# InverterControl_RevA.net
KiCad netlist of a schematic drawn in EAGLE
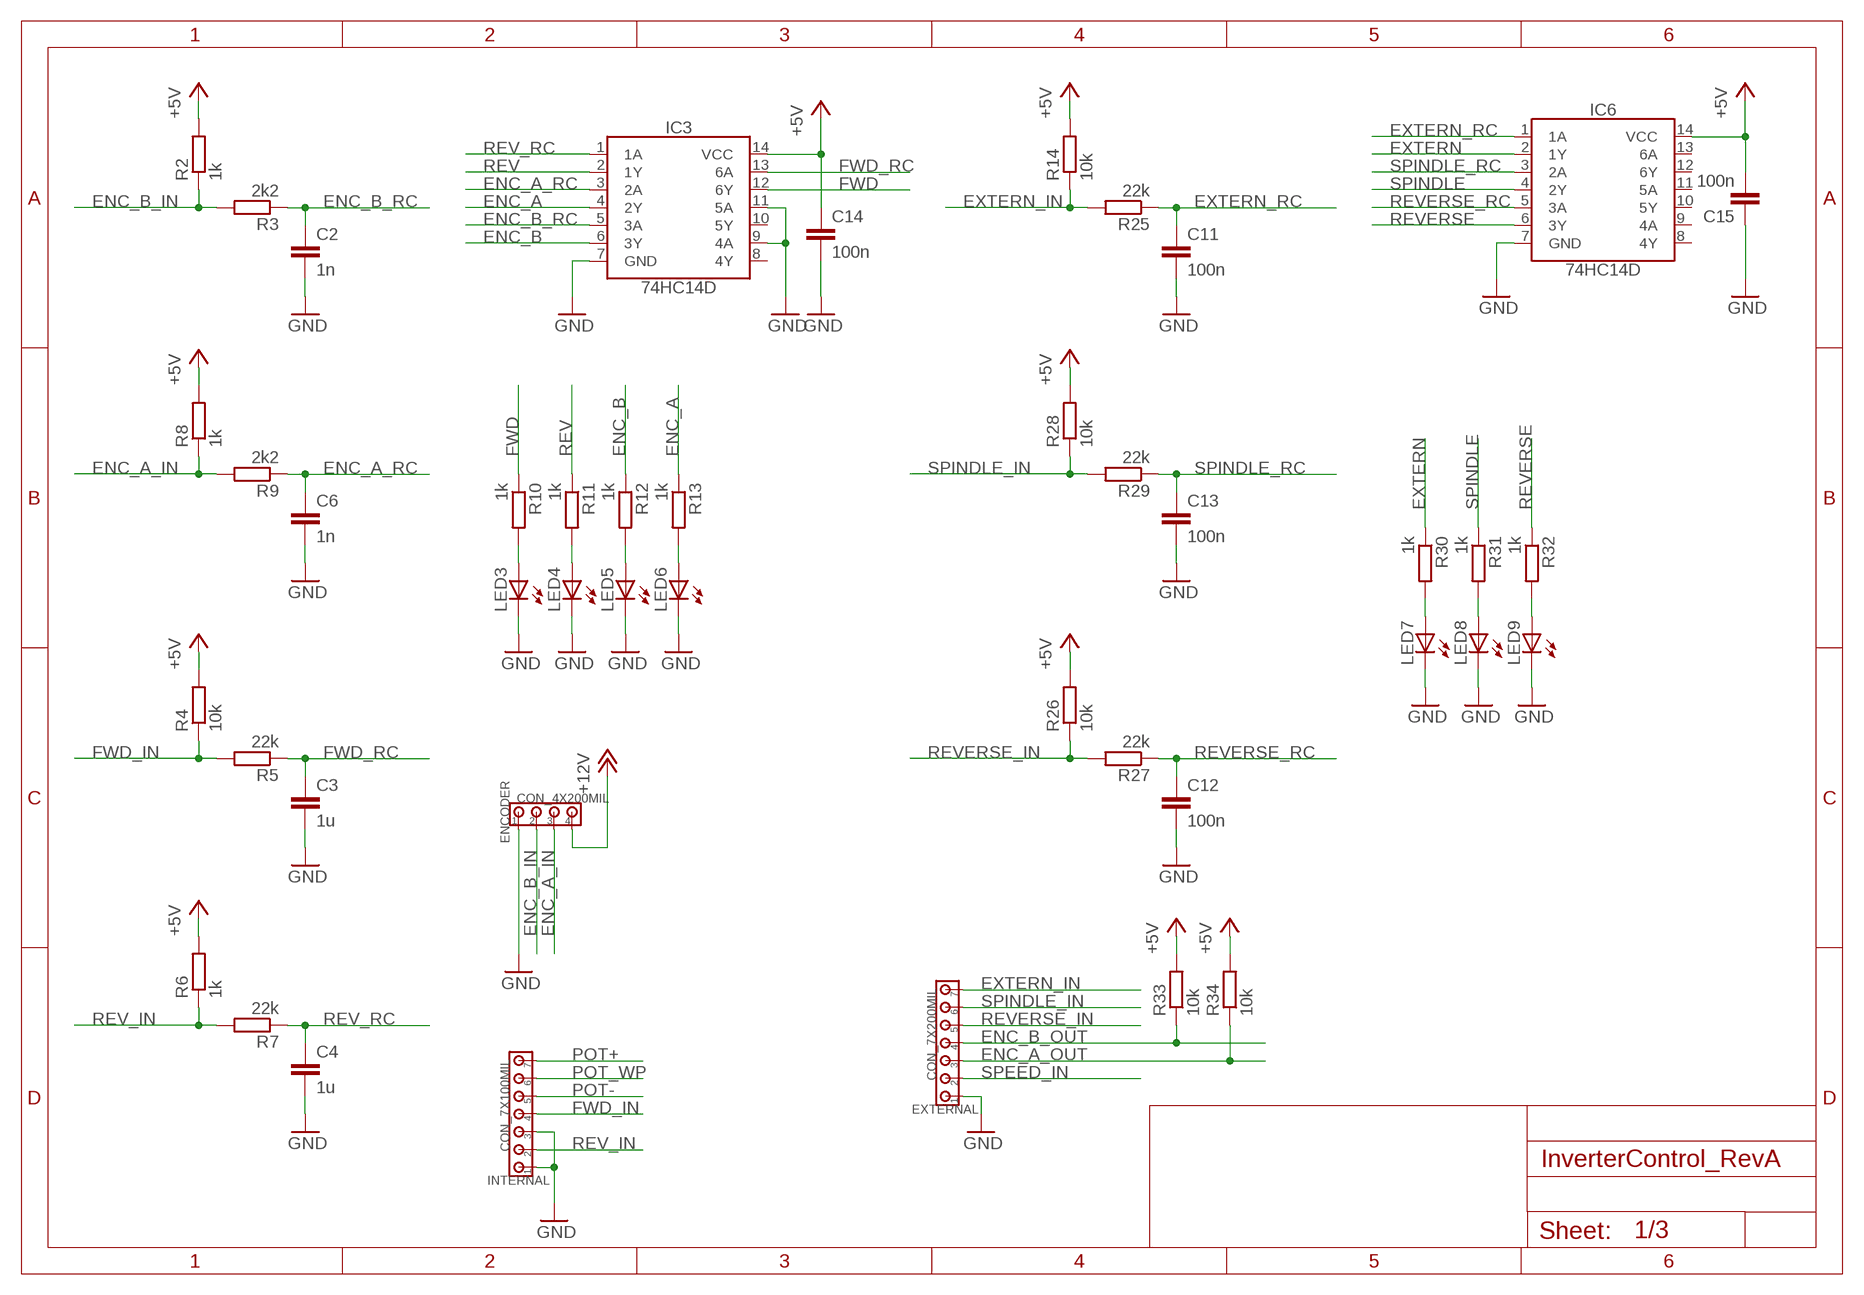
[diagram p0: schematic, sheet 1]
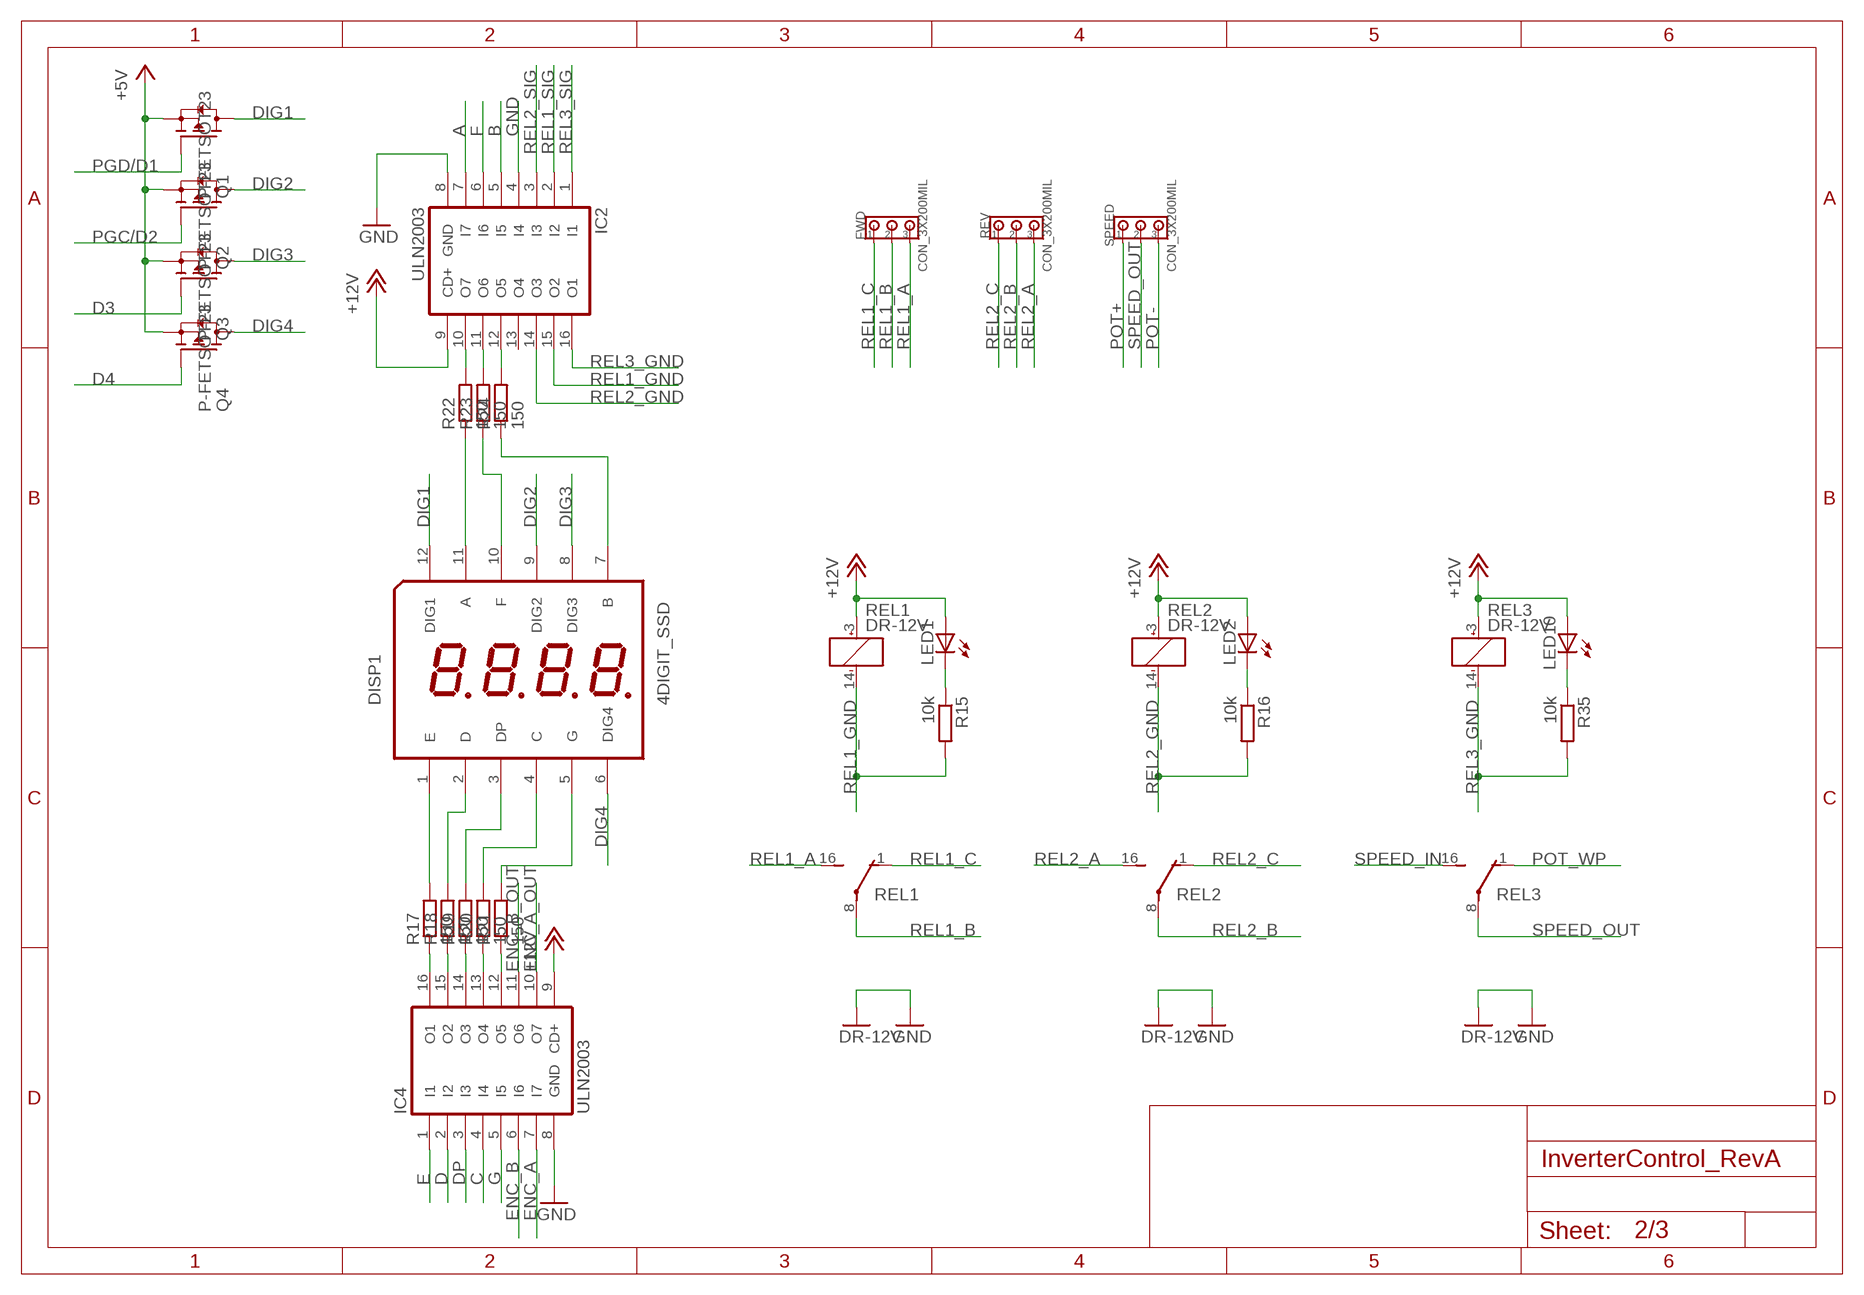
[diagram p1: schematic, sheet 2]
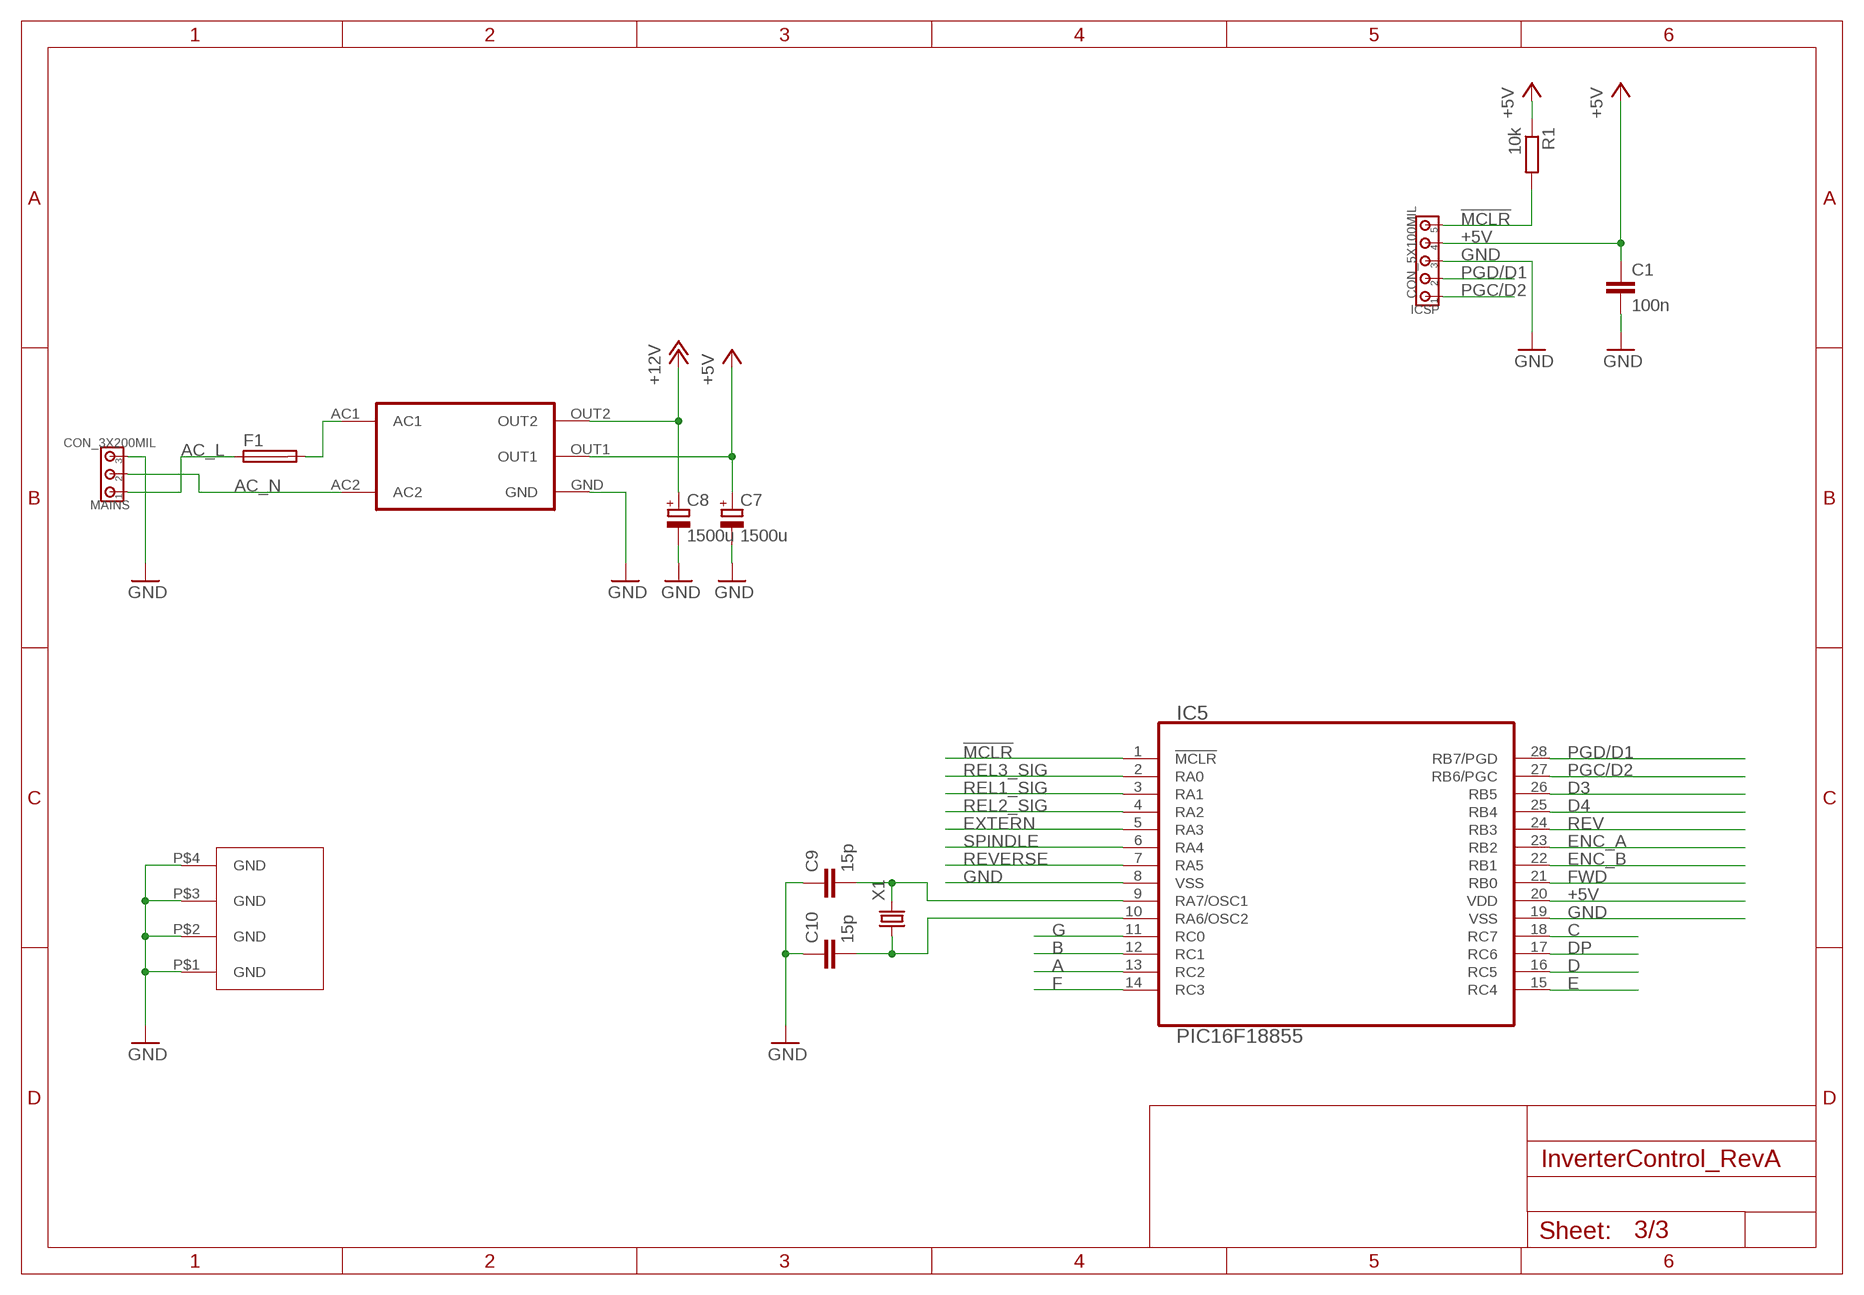
[diagram p2: schematic, sheet 3]

(export (version "E")
  (design (tool "Eeschema 10.0.6"))
  (components
    (comp (ref "ACDC1")
      (value "MYRRA47246")
      (footprint "eagle-import:MYRRA47000")
      (libsource (lib "eagle-import") (part "MYRRA47246"))
    )
    (comp (ref "C1")
      (value "100n")
      (footprint "eagle-import:C0805")
      (libsource (lib "eagle-import") (part "CC0805"))
    )
    (comp (ref "C7")
      (value "1500u")
      (footprint "eagle-import:10MM")
      (libsource (lib "eagle-import") (part "C_POLARIZED10MM"))
    )
    (comp (ref "C8")
      (value "1500u")
      (footprint "eagle-import:10MM")
      (libsource (lib "eagle-import") (part "C_POLARIZED10MM"))
    )
    (comp (ref "C9")
      (value "15p")
      (footprint "eagle-import:C0805")
      (libsource (lib "eagle-import") (part "CC0805"))
    )
    (comp (ref "C10")
      (value "15p")
      (footprint "eagle-import:C0805")
      (libsource (lib "eagle-import") (part "CC0805"))
    )
    (comp (ref "F1")
      (value "SH22,5")
      (footprint "eagle-import:SH22,5")
      (fields (field (name "MF") "SCHURTER") (field (name "MPN") "0031.8201"))
      (libsource (lib "eagle-import") (part "SH22,5"))
    )
    (comp (ref "IC5")
      (value "PIC16F18855")
      (footprint "eagle-import:SO28W")
      (libsource (lib "eagle-import") (part "PIC16F18855"))
    )
    (comp (ref "ICSP")
      (value "CON_5X100MIL")
      (footprint "eagle-import:100MIL_5X")
      (libsource (lib "eagle-import") (part "CON_5X100MIL"))
    )
    (comp (ref "MAINS")
      (value "CON_3X200MIL")
      (footprint "eagle-import:200MIL_3X")
      (libsource (lib "eagle-import") (part "CON_3X200MIL"))
    )
    (comp (ref "R1")
      (value "10k")
      (footprint "eagle-import:R0805")
      (libsource (lib "eagle-import") (part "RESISTORR0805"))
    )
    (comp (ref "U$1")
      (value "PCB_SPEED_METER")
      (footprint "eagle-import:PBC_SPEED_METER")
      (libsource (lib "eagle-import") (part "PCB_SPEED_METER"))
    )
    (comp (ref "X1")
      (value "CRYSTAL5X3.2MM")
      (footprint "eagle-import:5X3.2MM")
      (libsource (lib "eagle-import") (part "CRYSTAL5X3.2MM"))
    )
    (comp (ref "DISP1")
      (value "4DIGIT_SSD")
      (footprint "eagle-import:4DIGIT_SSD")
      (libsource (lib "eagle-import") (part "4DIGIT_SSD"))
    )
    (comp (ref "FWD")
      (value "CON_3X200MIL")
      (footprint "eagle-import:200MIL_3X")
      (libsource (lib "eagle-import") (part "CON_3X200MIL"))
    )
    (comp (ref "IC2")
      (value "ULN2003")
      (footprint "eagle-import:SO16")
      (libsource (lib "eagle-import") (part "ULN2003"))
    )
    (comp (ref "IC4")
      (value "ULN2003")
      (footprint "eagle-import:SO16")
      (libsource (lib "eagle-import") (part "ULN2003"))
    )
    (comp (ref "LED1")
      (value "LED0805")
      (footprint "eagle-import:LED0805")
      (libsource (lib "eagle-import") (part "LED0805"))
    )
    (comp (ref "LED2")
      (value "LED0805")
      (footprint "eagle-import:LED0805")
      (libsource (lib "eagle-import") (part "LED0805"))
    )
    (comp (ref "LED10")
      (value "LED0805")
      (footprint "eagle-import:LED0805")
      (libsource (lib "eagle-import") (part "LED0805"))
    )
    (comp (ref "Q1")
      (value "P-FETSOT23")
      (footprint "eagle-import:SOT23")
      (libsource (lib "eagle-import") (part "P-FETSOT23"))
    )
    (comp (ref "Q2")
      (value "P-FETSOT23")
      (footprint "eagle-import:SOT23")
      (libsource (lib "eagle-import") (part "P-FETSOT23"))
    )
    (comp (ref "Q3")
      (value "P-FETSOT23")
      (footprint "eagle-import:SOT23")
      (libsource (lib "eagle-import") (part "P-FETSOT23"))
    )
    (comp (ref "Q4")
      (value "P-FETSOT23")
      (footprint "eagle-import:SOT23")
      (libsource (lib "eagle-import") (part "P-FETSOT23"))
    )
    (comp (ref "R15")
      (value "10k")
      (footprint "eagle-import:R0805")
      (libsource (lib "eagle-import") (part "RESISTORR0805"))
    )
    (comp (ref "R16")
      (value "10k")
      (footprint "eagle-import:R0805")
      (libsource (lib "eagle-import") (part "RESISTORR0805"))
    )
    (comp (ref "R17")
      (value "150")
      (footprint "eagle-import:R0805")
      (libsource (lib "eagle-import") (part "RESISTORR0805"))
    )
    (comp (ref "R18")
      (value "150")
      (footprint "eagle-import:R0805")
      (libsource (lib "eagle-import") (part "RESISTORR0805"))
    )
    (comp (ref "R19")
      (value "150")
      (footprint "eagle-import:R0805")
      (libsource (lib "eagle-import") (part "RESISTORR0805"))
    )
    (comp (ref "R20")
      (value "150")
      (footprint "eagle-import:R0805")
      (libsource (lib "eagle-import") (part "RESISTORR0805"))
    )
    (comp (ref "R21")
      (value "150")
      (footprint "eagle-import:R0805")
      (libsource (lib "eagle-import") (part "RESISTORR0805"))
    )
    (comp (ref "R22")
      (value "150")
      (footprint "eagle-import:R0805")
      (libsource (lib "eagle-import") (part "RESISTORR0805"))
    )
    (comp (ref "R23")
      (value "150")
      (footprint "eagle-import:R0805")
      (libsource (lib "eagle-import") (part "RESISTORR0805"))
    )
    (comp (ref "R24")
      (value "150")
      (footprint "eagle-import:R0805")
      (libsource (lib "eagle-import") (part "RESISTORR0805"))
    )
    (comp (ref "R35")
      (value "10k")
      (footprint "eagle-import:R0805")
      (libsource (lib "eagle-import") (part "RESISTORR0805"))
    )
    (comp (ref "REL1")
      (value "DR-12V")
      (footprint "eagle-import:DR-12V")
      (libsource (lib "eagle-import") (part "DR-12V"))
    )
    (comp (ref "REL2")
      (value "DR-12V")
      (footprint "eagle-import:DR-12V")
      (libsource (lib "eagle-import") (part "DR-12V"))
    )
    (comp (ref "REL3")
      (value "DR-12V")
      (footprint "eagle-import:DR-12V")
      (libsource (lib "eagle-import") (part "DR-12V"))
    )
    (comp (ref "REV")
      (value "CON_3X200MIL")
      (footprint "eagle-import:200MIL_3X")
      (libsource (lib "eagle-import") (part "CON_3X200MIL"))
    )
    (comp (ref "SPEED")
      (value "CON_3X200MIL")
      (footprint "eagle-import:200MIL_3X")
      (libsource (lib "eagle-import") (part "CON_3X200MIL"))
    )
    (comp (ref "C2")
      (value "1n")
      (footprint "eagle-import:C0805")
      (libsource (lib "eagle-import") (part "CC0805"))
    )
    (comp (ref "C3")
      (value "1u")
      (footprint "eagle-import:C0805")
      (libsource (lib "eagle-import") (part "CC0805"))
    )
    (comp (ref "C4")
      (value "1u")
      (footprint "eagle-import:C0805")
      (libsource (lib "eagle-import") (part "CC0805"))
    )
    (comp (ref "C6")
      (value "1n")
      (footprint "eagle-import:C0805")
      (libsource (lib "eagle-import") (part "CC0805"))
    )
    (comp (ref "C11")
      (value "100n")
      (footprint "eagle-import:C0805")
      (libsource (lib "eagle-import") (part "CC0805"))
    )
    (comp (ref "C12")
      (value "100n")
      (footprint "eagle-import:C0805")
      (libsource (lib "eagle-import") (part "CC0805"))
    )
    (comp (ref "C13")
      (value "100n")
      (footprint "eagle-import:C0805")
      (libsource (lib "eagle-import") (part "CC0805"))
    )
    (comp (ref "C14")
      (value "100n")
      (footprint "eagle-import:C0805")
      (libsource (lib "eagle-import") (part "CC0805"))
    )
    (comp (ref "C15")
      (value "100n")
      (footprint "eagle-import:C0805")
      (libsource (lib "eagle-import") (part "CC0805"))
    )
    (comp (ref "ENCODER")
      (value "CON_4X200MIL")
      (footprint "eagle-import:200MIL_4X")
      (libsource (lib "eagle-import") (part "CON_4X200MIL"))
    )
    (comp (ref "EXTERNAL")
      (value "CON_7X200MIL")
      (footprint "eagle-import:200MIL_7X")
      (libsource (lib "eagle-import") (part "CON_7X200MIL"))
    )
    (comp (ref "IC3")
      (value "74HC14D")
      (footprint "eagle-import:SO14")
      (libsource (lib "eagle-import") (part "74HC14D"))
    )
    (comp (ref "IC6")
      (value "74HC14D")
      (footprint "eagle-import:SO14")
      (libsource (lib "eagle-import") (part "74HC14D"))
    )
    (comp (ref "INTERNAL")
      (value "CON_7X100MIL")
      (footprint "eagle-import:100MIL_7X")
      (libsource (lib "eagle-import") (part "CON_7X100MIL"))
    )
    (comp (ref "LED3")
      (value "LED0805")
      (footprint "eagle-import:LED0805")
      (libsource (lib "eagle-import") (part "LED0805"))
    )
    (comp (ref "LED4")
      (value "LED0805")
      (footprint "eagle-import:LED0805")
      (libsource (lib "eagle-import") (part "LED0805"))
    )
    (comp (ref "LED5")
      (value "LED0805")
      (footprint "eagle-import:LED0805")
      (libsource (lib "eagle-import") (part "LED0805"))
    )
    (comp (ref "LED6")
      (value "LED0805")
      (footprint "eagle-import:LED0805")
      (libsource (lib "eagle-import") (part "LED0805"))
    )
    (comp (ref "LED7")
      (value "LED0805")
      (footprint "eagle-import:LED0805")
      (libsource (lib "eagle-import") (part "LED0805"))
    )
    (comp (ref "LED8")
      (value "LED0805")
      (footprint "eagle-import:LED0805")
      (libsource (lib "eagle-import") (part "LED0805"))
    )
    (comp (ref "LED9")
      (value "LED0805")
      (footprint "eagle-import:LED0805")
      (libsource (lib "eagle-import") (part "LED0805"))
    )
    (comp (ref "R2")
      (value "1k")
      (footprint "eagle-import:R0805")
      (libsource (lib "eagle-import") (part "RESISTORR0805"))
    )
    (comp (ref "R3")
      (value "2k2")
      (footprint "eagle-import:R0805")
      (libsource (lib "eagle-import") (part "RESISTORR0805"))
    )
    (comp (ref "R4")
      (value "10k")
      (footprint "eagle-import:R0805")
      (libsource (lib "eagle-import") (part "RESISTORR0805"))
    )
    (comp (ref "R5")
      (value "22k")
      (footprint "eagle-import:R0805")
      (libsource (lib "eagle-import") (part "RESISTORR0805"))
    )
    (comp (ref "R6")
      (value "1k")
      (footprint "eagle-import:R0805")
      (libsource (lib "eagle-import") (part "RESISTORR0805"))
    )
    (comp (ref "R7")
      (value "22k")
      (footprint "eagle-import:R0805")
      (libsource (lib "eagle-import") (part "RESISTORR0805"))
    )
    (comp (ref "R8")
      (value "1k")
      (footprint "eagle-import:R0805")
      (libsource (lib "eagle-import") (part "RESISTORR0805"))
    )
    (comp (ref "R9")
      (value "2k2")
      (footprint "eagle-import:R0805")
      (libsource (lib "eagle-import") (part "RESISTORR0805"))
    )
    (comp (ref "R10")
      (value "1k")
      (footprint "eagle-import:R0805")
      (libsource (lib "eagle-import") (part "RESISTORR0805"))
    )
    (comp (ref "R11")
      (value "1k")
      (footprint "eagle-import:R0805")
      (libsource (lib "eagle-import") (part "RESISTORR0805"))
    )
    (comp (ref "R12")
      (value "1k")
      (footprint "eagle-import:R0805")
      (libsource (lib "eagle-import") (part "RESISTORR0805"))
    )
    (comp (ref "R13")
      (value "1k")
      (footprint "eagle-import:R0805")
      (libsource (lib "eagle-import") (part "RESISTORR0805"))
    )
    (comp (ref "R14")
      (value "10k")
      (footprint "eagle-import:R0805")
      (libsource (lib "eagle-import") (part "RESISTORR0805"))
    )
    (comp (ref "R25")
      (value "22k")
      (footprint "eagle-import:R0805")
      (libsource (lib "eagle-import") (part "RESISTORR0805"))
    )
    (comp (ref "R26")
      (value "10k")
      (footprint "eagle-import:R0805")
      (libsource (lib "eagle-import") (part "RESISTORR0805"))
    )
    (comp (ref "R27")
      (value "22k")
      (footprint "eagle-import:R0805")
      (libsource (lib "eagle-import") (part "RESISTORR0805"))
    )
    (comp (ref "R28")
      (value "10k")
      (footprint "eagle-import:R0805")
      (libsource (lib "eagle-import") (part "RESISTORR0805"))
    )
    (comp (ref "R29")
      (value "22k")
      (footprint "eagle-import:R0805")
      (libsource (lib "eagle-import") (part "RESISTORR0805"))
    )
    (comp (ref "R30")
      (value "1k")
      (footprint "eagle-import:R0805")
      (libsource (lib "eagle-import") (part "RESISTORR0805"))
    )
    (comp (ref "R31")
      (value "1k")
      (footprint "eagle-import:R0805")
      (libsource (lib "eagle-import") (part "RESISTORR0805"))
    )
    (comp (ref "R32")
      (value "1k")
      (footprint "eagle-import:R0805")
      (libsource (lib "eagle-import") (part "RESISTORR0805"))
    )
    (comp (ref "R33")
      (value "10k")
      (footprint "eagle-import:R0805")
      (libsource (lib "eagle-import") (part "RESISTORR0805"))
    )
    (comp (ref "R34")
      (value "10k")
      (footprint "eagle-import:R0805")
      (libsource (lib "eagle-import") (part "RESISTORR0805"))
    )
  )
  (nets
    (net (code "1") (name "+5V") (class "Default")
      (node (ref "ACDC1") (pin "OUT1") (pinfunction "OUT1_OUT1") (pintype "bidirectional"))
      (node (ref "C1") (pin "1") (pinfunction "1_1") (pintype "passive"))
      (node (ref "C14") (pin "1") (pinfunction "1_1") (pintype "passive"))
      (node (ref "C15") (pin "2") (pinfunction "2_2") (pintype "passive"))
      (node (ref "C7") (pin "+") (pinfunction "+_+") (pintype "passive"))
      (node (ref "IC3") (pin "14") (pinfunction "VCC_14") (pintype "power_in"))
      (node (ref "IC5") (pin "20") (pinfunction "VDD_20") (pintype "power_in"))
      (node (ref "IC6") (pin "14") (pinfunction "VCC_14") (pintype "power_in"))
      (node (ref "ICSP") (pin "4") (pinfunction "4_4") (pintype "passive"))
      (node (ref "Q1") (pin "2") (pinfunction "S_2") (pintype "passive"))
      (node (ref "Q2") (pin "2") (pinfunction "S_2") (pintype "passive"))
      (node (ref "Q3") (pin "2") (pinfunction "S_2") (pintype "passive"))
      (node (ref "Q4") (pin "2") (pinfunction "S_2") (pintype "passive"))
      (node (ref "R1") (pin "1") (pinfunction "1_1") (pintype "passive"))
      (node (ref "R14") (pin "2") (pinfunction "2_2") (pintype "passive"))
      (node (ref "R2") (pin "2") (pinfunction "2_2") (pintype "passive"))
      (node (ref "R26") (pin "2") (pinfunction "2_2") (pintype "passive"))
      (node (ref "R28") (pin "2") (pinfunction "2_2") (pintype "passive"))
      (node (ref "R33") (pin "2") (pinfunction "2_2") (pintype "passive"))
      (node (ref "R34") (pin "2") (pinfunction "2_2") (pintype "passive"))
      (node (ref "R4") (pin "2") (pinfunction "2_2") (pintype "passive"))
      (node (ref "R6") (pin "2") (pinfunction "2_2") (pintype "passive"))
      (node (ref "R8") (pin "2") (pinfunction "2_2") (pintype "passive"))
    )
    (net (code "2") (name "+12V") (class "Default")
      (node (ref "ACDC1") (pin "OUT2") (pinfunction "OUT2_OUT2") (pintype "bidirectional"))
      (node (ref "C8") (pin "+") (pinfunction "+_+") (pintype "passive"))
      (node (ref "ENCODER") (pin "4") (pinfunction "4_4") (pintype "passive"))
      (node (ref "IC2") (pin "9") (pinfunction "CD+_9") (pintype "passive"))
      (node (ref "IC4") (pin "9") (pinfunction "CD+_9") (pintype "passive"))
      (node (ref "LED1") (pin "A") (pinfunction "A_A") (pintype "passive"))
      (node (ref "LED10") (pin "A") (pinfunction "A_A") (pintype "passive"))
      (node (ref "LED2") (pin "A") (pinfunction "A_A") (pintype "passive"))
      (node (ref "REL1") (pin "3") (pinfunction "+_3") (pintype "passive"))
      (node (ref "REL2") (pin "3") (pinfunction "+_3") (pintype "passive"))
      (node (ref "REL3") (pin "3") (pinfunction "+_3") (pintype "passive"))
    )
    (net (code "3") (name "A") (class "Default")
      (node (ref "IC2") (pin "7") (pinfunction "I7_7") (pintype "input"))
      (node (ref "IC5") (pin "13") (pinfunction "RC2_13") (pintype "bidirectional"))
    )
    (net (code "4") (name "AC_L") (class "Default")
      (node (ref "F1") (pin "1") (pinfunction "1_1") (pintype "passive"))
      (node (ref "MAINS") (pin "1") (pinfunction "1_1") (pintype "passive"))
    )
    (net (code "5") (name "AC_N") (class "Default")
      (node (ref "ACDC1") (pin "AC2") (pinfunction "AC2_AC2") (pintype "power_in"))
      (node (ref "MAINS") (pin "2") (pinfunction "2_2") (pintype "passive"))
    )
    (net (code "6") (name "B") (class "Default")
      (node (ref "IC2") (pin "5") (pinfunction "I5_5") (pintype "input"))
      (node (ref "IC5") (pin "12") (pinfunction "RC1_12") (pintype "bidirectional"))
    )
    (net (code "7") (name "C") (class "Default")
      (node (ref "IC4") (pin "4") (pinfunction "I4_4") (pintype "input"))
      (node (ref "IC5") (pin "18") (pinfunction "RC7_18") (pintype "bidirectional"))
    )
    (net (code "8") (name "D") (class "Default")
      (node (ref "IC4") (pin "2") (pinfunction "I2_2") (pintype "input"))
      (node (ref "IC5") (pin "16") (pinfunction "RC5_16") (pintype "bidirectional"))
    )
    (net (code "9") (name "D3") (class "Default")
      (node (ref "IC5") (pin "26") (pinfunction "RB5_26") (pintype "bidirectional"))
      (node (ref "Q3") (pin "1") (pinfunction "G_1") (pintype "passive"))
    )
    (net (code "10") (name "D4") (class "Default")
      (node (ref "IC5") (pin "25") (pinfunction "RB4_25") (pintype "bidirectional"))
      (node (ref "Q4") (pin "1") (pinfunction "G_1") (pintype "passive"))
    )
    (net (code "11") (name "DIG1") (class "Default")
      (node (ref "DISP1") (pin "12") (pinfunction "DIG1_12") (pintype "bidirectional"))
      (node (ref "Q1") (pin "3") (pinfunction "D_3") (pintype "passive"))
    )
    (net (code "12") (name "DIG2") (class "Default")
      (node (ref "DISP1") (pin "9") (pinfunction "DIG2_9") (pintype "bidirectional"))
      (node (ref "Q2") (pin "3") (pinfunction "D_3") (pintype "passive"))
    )
    (net (code "13") (name "DIG3") (class "Default")
      (node (ref "DISP1") (pin "8") (pinfunction "DIG3_8") (pintype "bidirectional"))
      (node (ref "Q3") (pin "3") (pinfunction "D_3") (pintype "passive"))
    )
    (net (code "14") (name "DIG4") (class "Default")
      (node (ref "DISP1") (pin "6") (pinfunction "DIG4_6") (pintype "bidirectional"))
      (node (ref "Q4") (pin "3") (pinfunction "D_3") (pintype "passive"))
    )
    (net (code "15") (name "DP") (class "Default")
      (node (ref "IC4") (pin "3") (pinfunction "I3_3") (pintype "input"))
      (node (ref "IC5") (pin "17") (pinfunction "RC6_17") (pintype "bidirectional"))
    )
    (net (code "16") (name "E") (class "Default")
      (node (ref "IC4") (pin "1") (pinfunction "I1_1") (pintype "input"))
      (node (ref "IC5") (pin "15") (pinfunction "RC4_15") (pintype "bidirectional"))
    )
    (net (code "17") (name "ENC_A") (class "Default")
      (node (ref "IC3") (pin "4") (pinfunction "2Y_4") (pintype "input"))
      (node (ref "IC4") (pin "7") (pinfunction "I7_7") (pintype "input"))
      (node (ref "IC5") (pin "23") (pinfunction "RB2_23") (pintype "bidirectional"))
      (node (ref "R13") (pin "1") (pinfunction "1_1") (pintype "passive"))
    )
    (net (code "18") (name "ENC_A_IN") (class "Default")
      (node (ref "ENCODER") (pin "3") (pinfunction "3_3") (pintype "passive"))
      (node (ref "R8") (pin "1") (pinfunction "1_1") (pintype "passive"))
      (node (ref "R9") (pin "2") (pinfunction "2_2") (pintype "passive"))
    )
    (net (code "19") (name "ENC_A_OUT") (class "Default")
      (node (ref "EXTERNAL") (pin "3") (pinfunction "P$3_3") (pintype "passive"))
      (node (ref "IC4") (pin "10") (pinfunction "O7_10") (pintype "open_collector"))
      (node (ref "R34") (pin "1") (pinfunction "1_1") (pintype "passive"))
    )
    (net (code "20") (name "ENC_A_RC") (class "Default")
      (node (ref "C6") (pin "1") (pinfunction "1_1") (pintype "passive"))
      (node (ref "IC3") (pin "3") (pinfunction "2A_3") (pintype "input"))
      (node (ref "R9") (pin "1") (pinfunction "1_1") (pintype "passive"))
    )
    (net (code "21") (name "ENC_B") (class "Default")
      (node (ref "IC3") (pin "6") (pinfunction "3Y_6") (pintype "input"))
      (node (ref "IC4") (pin "6") (pinfunction "I6_6") (pintype "input"))
      (node (ref "IC5") (pin "22") (pinfunction "RB1_22") (pintype "bidirectional"))
      (node (ref "R12") (pin "1") (pinfunction "1_1") (pintype "passive"))
    )
    (net (code "22") (name "ENC_B_IN") (class "Default")
      (node (ref "ENCODER") (pin "2") (pinfunction "2_2") (pintype "passive"))
      (node (ref "R2") (pin "1") (pinfunction "1_1") (pintype "passive"))
      (node (ref "R3") (pin "2") (pinfunction "2_2") (pintype "passive"))
    )
    (net (code "23") (name "ENC_B_OUT") (class "Default")
      (node (ref "EXTERNAL") (pin "4") (pinfunction "P$4_4") (pintype "passive"))
      (node (ref "IC4") (pin "11") (pinfunction "O6_11") (pintype "open_collector"))
      (node (ref "R33") (pin "1") (pinfunction "1_1") (pintype "passive"))
    )
    (net (code "24") (name "ENC_B_RC") (class "Default")
      (node (ref "C2") (pin "1") (pinfunction "1_1") (pintype "passive"))
      (node (ref "IC3") (pin "5") (pinfunction "3A_5") (pintype "input"))
      (node (ref "R3") (pin "1") (pinfunction "1_1") (pintype "passive"))
    )
    (net (code "25") (name "EXTERN") (class "Default")
      (node (ref "IC5") (pin "5") (pinfunction "RA3_5") (pintype "bidirectional"))
      (node (ref "IC6") (pin "2") (pinfunction "1Y_2") (pintype "input"))
      (node (ref "R30") (pin "1") (pinfunction "1_1") (pintype "passive"))
    )
    (net (code "26") (name "EXTERN_IN") (class "Default")
      (node (ref "EXTERNAL") (pin "7") (pinfunction "P$7_7") (pintype "passive"))
      (node (ref "R14") (pin "1") (pinfunction "1_1") (pintype "passive"))
      (node (ref "R25") (pin "2") (pinfunction "2_2") (pintype "passive"))
    )
    (net (code "27") (name "EXTERN_RC") (class "Default")
      (node (ref "C11") (pin "1") (pinfunction "1_1") (pintype "passive"))
      (node (ref "IC6") (pin "1") (pinfunction "1A_1") (pintype "input"))
      (node (ref "R25") (pin "1") (pinfunction "1_1") (pintype "passive"))
    )
    (net (code "28") (name "F") (class "Default")
      (node (ref "IC2") (pin "6") (pinfunction "I6_6") (pintype "input"))
      (node (ref "IC5") (pin "14") (pinfunction "RC3_14") (pintype "power_in"))
    )
    (net (code "29") (name "FWD") (class "Default")
      (node (ref "IC3") (pin "12") (pinfunction "6Y_12") (pintype "bidirectional"))
      (node (ref "IC5") (pin "21") (pinfunction "RB0_21") (pintype "bidirectional"))
      (node (ref "R10") (pin "1") (pinfunction "1_1") (pintype "passive"))
    )
    (net (code "30") (name "FWD_IN") (class "Default")
      (node (ref "INTERNAL") (pin "4") (pinfunction "P$4_4") (pintype "passive"))
      (node (ref "R4") (pin "1") (pinfunction "1_1") (pintype "passive"))
      (node (ref "R5") (pin "2") (pinfunction "2_2") (pintype "passive"))
    )
    (net (code "31") (name "FWD_RC") (class "Default")
      (node (ref "C3") (pin "1") (pinfunction "1_1") (pintype "passive"))
      (node (ref "IC3") (pin "13") (pinfunction "6A_13") (pintype "bidirectional"))
      (node (ref "R5") (pin "1") (pinfunction "1_1") (pintype "passive"))
    )
    (net (code "32") (name "G") (class "Default")
      (node (ref "IC4") (pin "5") (pinfunction "I5_5") (pintype "input"))
      (node (ref "IC5") (pin "11") (pinfunction "RC0_11") (pintype "bidirectional"))
    )
    (net (code "33") (name "GND") (class "Default")
      (node (ref "ACDC1") (pin "GND") (pinfunction "GND_GND") (pintype "bidirectional"))
      (node (ref "C1") (pin "2") (pinfunction "2_2") (pintype "passive"))
      (node (ref "C10") (pin "1") (pinfunction "1_1") (pintype "passive"))
      (node (ref "C11") (pin "2") (pinfunction "2_2") (pintype "passive"))
      (node (ref "C12") (pin "2") (pinfunction "2_2") (pintype "passive"))
      (node (ref "C13") (pin "2") (pinfunction "2_2") (pintype "passive"))
      (node (ref "C14") (pin "2") (pinfunction "2_2") (pintype "passive"))
      (node (ref "C15") (pin "1") (pinfunction "1_1") (pintype "passive"))
      (node (ref "C2") (pin "2") (pinfunction "2_2") (pintype "passive"))
      (node (ref "C3") (pin "2") (pinfunction "2_2") (pintype "passive"))
      (node (ref "C4") (pin "2") (pinfunction "2_2") (pintype "passive"))
      (node (ref "C6") (pin "2") (pinfunction "2_2") (pintype "passive"))
      (node (ref "C7") (pin "-") (pinfunction "-_-") (pintype "passive"))
      (node (ref "C8") (pin "-") (pinfunction "-_-") (pintype "passive"))
      (node (ref "C9") (pin "1") (pinfunction "1_1") (pintype "passive"))
      (node (ref "ENCODER") (pin "1") (pinfunction "1_1") (pintype "passive"))
      (node (ref "EXTERNAL") (pin "1") (pinfunction "P$1_1") (pintype "passive"))
      (node (ref "IC2") (pin "4") (pinfunction "I4_4") (pintype "input"))
      (node (ref "IC2") (pin "8") (pinfunction "GND_8") (pintype "power_in"))
      (node (ref "IC3") (pin "11") (pinfunction "5A_11") (pintype "bidirectional"))
      (node (ref "IC3") (pin "7") (pinfunction "GND_7") (pintype "bidirectional"))
      (node (ref "IC3") (pin "9") (pinfunction "4A_9") (pintype "bidirectional"))
      (node (ref "IC4") (pin "8") (pinfunction "GND_8") (pintype "power_in"))
      (node (ref "IC5") (pin "19") (pinfunction "VSS_19") (pintype "passive"))
      (node (ref "IC5") (pin "8") (pinfunction "VSS_8") (pintype "passive"))
      (node (ref "IC6") (pin "7") (pinfunction "GND_7") (pintype "bidirectional"))
      (node (ref "ICSP") (pin "3") (pinfunction "3_3") (pintype "passive"))
      (node (ref "INTERNAL") (pin "1") (pinfunction "P$1_1") (pintype "passive"))
      (node (ref "INTERNAL") (pin "3") (pinfunction "P$3_3") (pintype "passive"))
      (node (ref "LED3") (pin "C") (pinfunction "C_C") (pintype "passive"))
      (node (ref "LED4") (pin "C") (pinfunction "C_C") (pintype "passive"))
      (node (ref "LED5") (pin "C") (pinfunction "C_C") (pintype "passive"))
      (node (ref "LED6") (pin "C") (pinfunction "C_C") (pintype "passive"))
      (node (ref "LED7") (pin "C") (pinfunction "C_C") (pintype "passive"))
      (node (ref "LED8") (pin "C") (pinfunction "C_C") (pintype "passive"))
      (node (ref "LED9") (pin "C") (pinfunction "C_C") (pintype "passive"))
      (node (ref "MAINS") (pin "3") (pinfunction "3_3") (pintype "passive"))
      (node (ref "REL1") (pin "9") (pinfunction "GND_9") (pintype "power_in"))
      (node (ref "REL2") (pin "9") (pinfunction "GND_9") (pintype "power_in"))
      (node (ref "REL3") (pin "9") (pinfunction "GND_9") (pintype "power_in"))
      (node (ref "U$1") (pin "P$1") (pinfunction "GND_P$1") (pintype "bidirectional"))
      (node (ref "U$1") (pin "P$2") (pinfunction "GND_P$2") (pintype "bidirectional"))
      (node (ref "U$1") (pin "P$3") (pinfunction "GND_P$3") (pintype "bidirectional"))
      (node (ref "U$1") (pin "P$4") (pinfunction "GND_P$4") (pintype "bidirectional"))
    )
    (net (code "34") (name "Net-(ACDC1-PadAC1)") (class "Default")
      (node (ref "ACDC1") (pin "AC1") (pinfunction "AC1_AC1") (pintype "power_in"))
      (node (ref "F1") (pin "2") (pinfunction "2_2") (pintype "passive"))
    )
    (net (code "35") (name "Net-(DISP1-A)") (class "Default")
      (node (ref "DISP1") (pin "11") (pinfunction "A_11") (pintype "bidirectional"))
      (node (ref "R22") (pin "1") (pinfunction "1_1") (pintype "passive"))
    )
    (net (code "36") (name "Net-(DISP1-B)") (class "Default")
      (node (ref "DISP1") (pin "7") (pinfunction "B_7") (pintype "bidirectional"))
      (node (ref "R24") (pin "1") (pinfunction "1_1") (pintype "passive"))
    )
    (net (code "37") (name "Net-(DISP1-C)") (class "Default")
      (node (ref "DISP1") (pin "4") (pinfunction "C_4") (pintype "bidirectional"))
      (node (ref "R20") (pin "2") (pinfunction "2_2") (pintype "passive"))
    )
    (net (code "38") (name "Net-(DISP1-D)") (class "Default")
      (node (ref "DISP1") (pin "2") (pinfunction "D_2") (pintype "bidirectional"))
      (node (ref "R18") (pin "2") (pinfunction "2_2") (pintype "passive"))
    )
    (net (code "39") (name "Net-(DISP1-DP)") (class "Default")
      (node (ref "DISP1") (pin "3") (pinfunction "DP_3") (pintype "bidirectional"))
      (node (ref "R19") (pin "2") (pinfunction "2_2") (pintype "passive"))
    )
    (net (code "40") (name "Net-(DISP1-E)") (class "Default")
      (node (ref "DISP1") (pin "1") (pinfunction "E_1") (pintype "bidirectional"))
      (node (ref "R17") (pin "2") (pinfunction "2_2") (pintype "passive"))
    )
    (net (code "41") (name "Net-(DISP1-F)") (class "Default")
      (node (ref "DISP1") (pin "10") (pinfunction "F_10") (pintype "bidirectional"))
      (node (ref "R23") (pin "1") (pinfunction "1_1") (pintype "passive"))
    )
    (net (code "42") (name "Net-(DISP1-G)") (class "Default")
      (node (ref "DISP1") (pin "5") (pinfunction "G_5") (pintype "bidirectional"))
      (node (ref "R21") (pin "2") (pinfunction "2_2") (pintype "passive"))
    )
    (net (code "43") (name "Net-(IC2-O5)") (class "Default")
      (node (ref "IC2") (pin "12") (pinfunction "O5_12") (pintype "open_collector"))
      (node (ref "R24") (pin "2") (pinfunction "2_2") (pintype "passive"))
    )
    (net (code "44") (name "Net-(IC2-O6)") (class "Default")
      (node (ref "IC2") (pin "11") (pinfunction "O6_11") (pintype "open_collector"))
      (node (ref "R23") (pin "2") (pinfunction "2_2") (pintype "passive"))
    )
    (net (code "45") (name "Net-(IC2-O7)") (class "Default")
      (node (ref "IC2") (pin "10") (pinfunction "O7_10") (pintype "open_collector"))
      (node (ref "R22") (pin "2") (pinfunction "2_2") (pintype "passive"))
    )
    (net (code "46") (name "Net-(IC4-O1)") (class "Default")
      (node (ref "IC4") (pin "16") (pinfunction "O1_16") (pintype "open_collector"))
      (node (ref "R17") (pin "1") (pinfunction "1_1") (pintype "passive"))
    )
    (net (code "47") (name "Net-(IC4-O2)") (class "Default")
      (node (ref "IC4") (pin "15") (pinfunction "O2_15") (pintype "open_collector"))
      (node (ref "R18") (pin "1") (pinfunction "1_1") (pintype "passive"))
    )
    (net (code "48") (name "Net-(IC4-O3)") (class "Default")
      (node (ref "IC4") (pin "14") (pinfunction "O3_14") (pintype "open_collector"))
      (node (ref "R19") (pin "1") (pinfunction "1_1") (pintype "passive"))
    )
    (net (code "49") (name "Net-(IC4-O4)") (class "Default")
      (node (ref "IC4") (pin "13") (pinfunction "O4_13") (pintype "open_collector"))
      (node (ref "R20") (pin "1") (pinfunction "1_1") (pintype "passive"))
    )
    (net (code "50") (name "Net-(IC4-O5)") (class "Default")
      (node (ref "IC4") (pin "12") (pinfunction "O5_12") (pintype "open_collector"))
      (node (ref "R21") (pin "1") (pinfunction "1_1") (pintype "passive"))
    )
    (net (code "51") (name "Net-(IC5-RA6{slash}OSC2)") (class "Default")
      (node (ref "C10") (pin "2") (pinfunction "2_2") (pintype "passive"))
      (node (ref "IC5") (pin "10") (pinfunction "RA6/OSC2_10") (pintype "bidirectional"))
      (node (ref "X1") (pin "1") (pinfunction "1_1") (pintype "passive"))
    )
    (net (code "52") (name "Net-(IC5-RA7{slash}OSC1)") (class "Default")
      (node (ref "C9") (pin "2") (pinfunction "2_2") (pintype "passive"))
      (node (ref "IC5") (pin "9") (pinfunction "RA7/OSC1_9") (pintype "bidirectional"))
      (node (ref "X1") (pin "2") (pinfunction "2_2") (pintype "passive"))
    )
    (net (code "53") (name "Net-(LED1-PadC)") (class "Default")
      (node (ref "LED1") (pin "C") (pinfunction "C_C") (pintype "passive"))
      (node (ref "R15") (pin "1") (pinfunction "1_1") (pintype "passive"))
    )
    (net (code "54") (name "Net-(LED2-PadC)") (class "Default")
      (node (ref "LED2") (pin "C") (pinfunction "C_C") (pintype "passive"))
      (node (ref "R16") (pin "1") (pinfunction "1_1") (pintype "passive"))
    )
    (net (code "55") (name "Net-(LED3-PadA)") (class "Default")
      (node (ref "LED3") (pin "A") (pinfunction "A_A") (pintype "passive"))
      (node (ref "R10") (pin "2") (pinfunction "2_2") (pintype "passive"))
    )
    (net (code "56") (name "Net-(LED4-PadA)") (class "Default")
      (node (ref "LED4") (pin "A") (pinfunction "A_A") (pintype "passive"))
      (node (ref "R11") (pin "2") (pinfunction "2_2") (pintype "passive"))
    )
    (net (code "57") (name "Net-(LED5-PadA)") (class "Default")
      (node (ref "LED5") (pin "A") (pinfunction "A_A") (pintype "passive"))
      (node (ref "R12") (pin "2") (pinfunction "2_2") (pintype "passive"))
    )
    (net (code "58") (name "Net-(LED6-PadA)") (class "Default")
      (node (ref "LED6") (pin "A") (pinfunction "A_A") (pintype "passive"))
      (node (ref "R13") (pin "2") (pinfunction "2_2") (pintype "passive"))
    )
    (net (code "59") (name "Net-(LED7-PadA)") (class "Default")
      (node (ref "LED7") (pin "A") (pinfunction "A_A") (pintype "passive"))
      (node (ref "R30") (pin "2") (pinfunction "2_2") (pintype "passive"))
    )
    (net (code "60") (name "Net-(LED8-PadA)") (class "Default")
      (node (ref "LED8") (pin "A") (pinfunction "A_A") (pintype "passive"))
      (node (ref "R31") (pin "2") (pinfunction "2_2") (pintype "passive"))
    )
    (net (code "61") (name "Net-(LED9-PadA)") (class "Default")
      (node (ref "LED9") (pin "A") (pinfunction "A_A") (pintype "passive"))
      (node (ref "R32") (pin "2") (pinfunction "2_2") (pintype "passive"))
    )
    (net (code "62") (name "Net-(LED10-PadC)") (class "Default")
      (node (ref "LED10") (pin "C") (pinfunction "C_C") (pintype "passive"))
      (node (ref "R35") (pin "1") (pinfunction "1_1") (pintype "passive"))
    )
    (net (code "63") (name "PGC{slash}D2") (class "Default")
      (node (ref "IC5") (pin "27") (pinfunction "RB6/PGC_27") (pintype "bidirectional"))
      (node (ref "ICSP") (pin "1") (pinfunction "1_1") (pintype "passive"))
      (node (ref "Q2") (pin "1") (pinfunction "G_1") (pintype "passive"))
    )
    (net (code "64") (name "PGD{slash}D1") (class "Default")
      (node (ref "IC5") (pin "28") (pinfunction "RB7/PGD_28") (pintype "bidirectional"))
      (node (ref "ICSP") (pin "2") (pinfunction "2_2") (pintype "passive"))
      (node (ref "Q1") (pin "1") (pinfunction "G_1") (pintype "passive"))
    )
    (net (code "65") (name "POT+") (class "Default")
      (node (ref "INTERNAL") (pin "7") (pinfunction "P$7_7") (pintype "passive"))
      (node (ref "SPEED") (pin "1") (pinfunction "1_1") (pintype "passive"))
    )
    (net (code "66") (name "POT-") (class "Default")
      (node (ref "INTERNAL") (pin "5") (pinfunction "P$5_5") (pintype "passive"))
      (node (ref "SPEED") (pin "3") (pinfunction "3_3") (pintype "passive"))
    )
    (net (code "67") (name "POT_WP") (class "Default")
      (node (ref "INTERNAL") (pin "6") (pinfunction "P$6_6") (pintype "passive"))
      (node (ref "REL3") (pin "1") (pinfunction "NC_1") (pintype "passive"))
    )
    (net (code "68") (name "REL1_A") (class "Default")
      (node (ref "FWD") (pin "3") (pinfunction "3_3") (pintype "passive"))
      (node (ref "REL1") (pin "16") (pinfunction "NO_16") (pintype "passive"))
    )
    (net (code "69") (name "REL1_B") (class "Default")
      (node (ref "FWD") (pin "2") (pinfunction "2_2") (pintype "passive"))
      (node (ref "REL1") (pin "8") (pinfunction "COM_8") (pintype "passive"))
    )
    (net (code "70") (name "REL1_C") (class "Default")
      (node (ref "FWD") (pin "1") (pinfunction "1_1") (pintype "passive"))
      (node (ref "REL1") (pin "1") (pinfunction "NC_1") (pintype "passive"))
    )
    (net (code "71") (name "REL1_GND") (class "Default")
      (node (ref "IC2") (pin "15") (pinfunction "O2_15") (pintype "open_collector"))
      (node (ref "R15") (pin "2") (pinfunction "2_2") (pintype "passive"))
      (node (ref "REL1") (pin "14") (pinfunction "-_14") (pintype "passive"))
    )
    (net (code "72") (name "REL1_SIG") (class "Default")
      (node (ref "IC2") (pin "2") (pinfunction "I2_2") (pintype "input"))
      (node (ref "IC5") (pin "3") (pinfunction "RA1_3") (pintype "bidirectional"))
    )
    (net (code "73") (name "REL2_A") (class "Default")
      (node (ref "REL2") (pin "16") (pinfunction "NO_16") (pintype "passive"))
      (node (ref "REV") (pin "3") (pinfunction "3_3") (pintype "passive"))
    )
    (net (code "74") (name "REL2_B") (class "Default")
      (node (ref "REL2") (pin "8") (pinfunction "COM_8") (pintype "passive"))
      (node (ref "REV") (pin "2") (pinfunction "2_2") (pintype "passive"))
    )
    (net (code "75") (name "REL2_C") (class "Default")
      (node (ref "REL2") (pin "1") (pinfunction "NC_1") (pintype "passive"))
      (node (ref "REV") (pin "1") (pinfunction "1_1") (pintype "passive"))
    )
    (net (code "76") (name "REL2_GND") (class "Default")
      (node (ref "IC2") (pin "14") (pinfunction "O3_14") (pintype "open_collector"))
      (node (ref "R16") (pin "2") (pinfunction "2_2") (pintype "passive"))
      (node (ref "REL2") (pin "14") (pinfunction "-_14") (pintype "passive"))
    )
    (net (code "77") (name "REL2_SIG") (class "Default")
      (node (ref "IC2") (pin "3") (pinfunction "I3_3") (pintype "input"))
      (node (ref "IC5") (pin "4") (pinfunction "RA2_4") (pintype "bidirectional"))
    )
    (net (code "78") (name "REL3_GND") (class "Default")
      (node (ref "IC2") (pin "16") (pinfunction "O1_16") (pintype "open_collector"))
      (node (ref "R35") (pin "2") (pinfunction "2_2") (pintype "passive"))
      (node (ref "REL3") (pin "14") (pinfunction "-_14") (pintype "passive"))
    )
    (net (code "79") (name "REL3_SIG") (class "Default")
      (node (ref "IC2") (pin "1") (pinfunction "I1_1") (pintype "input"))
      (node (ref "IC5") (pin "2") (pinfunction "RA0_2") (pintype "bidirectional"))
    )
    (net (code "80") (name "REV") (class "Default")
      (node (ref "IC3") (pin "2") (pinfunction "1Y_2") (pintype "input"))
      (node (ref "IC5") (pin "24") (pinfunction "RB3_24") (pintype "bidirectional"))
      (node (ref "R11") (pin "1") (pinfunction "1_1") (pintype "passive"))
    )
    (net (code "81") (name "REVERSE") (class "Default")
      (node (ref "IC5") (pin "7") (pinfunction "RA5_7") (pintype "bidirectional"))
      (node (ref "IC6") (pin "6") (pinfunction "3Y_6") (pintype "input"))
      (node (ref "R32") (pin "1") (pinfunction "1_1") (pintype "passive"))
    )
    (net (code "82") (name "REVERSE_IN") (class "Default")
      (node (ref "EXTERNAL") (pin "5") (pinfunction "P$5_5") (pintype "passive"))
      (node (ref "R26") (pin "1") (pinfunction "1_1") (pintype "passive"))
      (node (ref "R27") (pin "2") (pinfunction "2_2") (pintype "passive"))
    )
    (net (code "83") (name "REVERSE_RC") (class "Default")
      (node (ref "C12") (pin "1") (pinfunction "1_1") (pintype "passive"))
      (node (ref "IC6") (pin "5") (pinfunction "3A_5") (pintype "input"))
      (node (ref "R27") (pin "1") (pinfunction "1_1") (pintype "passive"))
    )
    (net (code "84") (name "REV_IN") (class "Default")
      (node (ref "INTERNAL") (pin "2") (pinfunction "P$2_2") (pintype "passive"))
      (node (ref "R6") (pin "1") (pinfunction "1_1") (pintype "passive"))
      (node (ref "R7") (pin "2") (pinfunction "2_2") (pintype "passive"))
    )
    (net (code "85") (name "REV_RC") (class "Default")
      (node (ref "C4") (pin "1") (pinfunction "1_1") (pintype "passive"))
      (node (ref "IC3") (pin "1") (pinfunction "1A_1") (pintype "input"))
      (node (ref "R7") (pin "1") (pinfunction "1_1") (pintype "passive"))
    )
    (net (code "86") (name "SPEED_IN") (class "Default")
      (node (ref "EXTERNAL") (pin "2") (pinfunction "P$2_2") (pintype "passive"))
      (node (ref "REL3") (pin "16") (pinfunction "NO_16") (pintype "passive"))
    )
    (net (code "87") (name "SPEED_OUT") (class "Default")
      (node (ref "REL3") (pin "8") (pinfunction "COM_8") (pintype "passive"))
      (node (ref "SPEED") (pin "2") (pinfunction "2_2") (pintype "passive"))
    )
    (net (code "88") (name "SPINDLE") (class "Default")
      (node (ref "IC5") (pin "6") (pinfunction "RA4_6") (pintype "power_in"))
      (node (ref "IC6") (pin "4") (pinfunction "2Y_4") (pintype "input"))
      (node (ref "R31") (pin "1") (pinfunction "1_1") (pintype "passive"))
    )
    (net (code "89") (name "SPINDLE_IN") (class "Default")
      (node (ref "EXTERNAL") (pin "6") (pinfunction "P$6_6") (pintype "passive"))
      (node (ref "R28") (pin "1") (pinfunction "1_1") (pintype "passive"))
      (node (ref "R29") (pin "2") (pinfunction "2_2") (pintype "passive"))
    )
    (net (code "90") (name "SPINDLE_RC") (class "Default")
      (node (ref "C13") (pin "1") (pinfunction "1_1") (pintype "passive"))
      (node (ref "IC6") (pin "3") (pinfunction "2A_3") (pintype "input"))
      (node (ref "R29") (pin "1") (pinfunction "1_1") (pintype "passive"))
    )
    (net (code "91") (name "unconnected-(IC2-O4-Pad13)") (class "Default")
      (node (ref "IC2") (pin "13") (pinfunction "O4_13") (pintype "open_collector"))
    )
    (net (code "92") (name "unconnected-(IC3-4Y-Pad8)") (class "Default")
      (node (ref "IC3") (pin "8") (pinfunction "4Y_8") (pintype "bidirectional"))
    )
    (net (code "93") (name "unconnected-(IC3-5Y-Pad10)") (class "Default")
      (node (ref "IC3") (pin "10") (pinfunction "5Y_10") (pintype "bidirectional"))
    )
    (net (code "94") (name "unconnected-(IC6-4A-Pad9)") (class "Default")
      (node (ref "IC6") (pin "9") (pinfunction "4A_9") (pintype "bidirectional"))
    )
    (net (code "95") (name "unconnected-(IC6-4Y-Pad8)") (class "Default")
      (node (ref "IC6") (pin "8") (pinfunction "4Y_8") (pintype "bidirectional"))
    )
    (net (code "96") (name "unconnected-(IC6-5A-Pad11)") (class "Default")
      (node (ref "IC6") (pin "11") (pinfunction "5A_11") (pintype "bidirectional"))
    )
    (net (code "97") (name "unconnected-(IC6-5Y-Pad10)") (class "Default")
      (node (ref "IC6") (pin "10") (pinfunction "5Y_10") (pintype "bidirectional"))
    )
    (net (code "98") (name "unconnected-(IC6-6A-Pad13)") (class "Default")
      (node (ref "IC6") (pin "13") (pinfunction "6A_13") (pintype "bidirectional"))
    )
    (net (code "99") (name "unconnected-(IC6-6Y-Pad12)") (class "Default")
      (node (ref "IC6") (pin "12") (pinfunction "6Y_12") (pintype "bidirectional"))
    )
    (net (code "100") (name "~{MCLR}") (class "Default")
      (node (ref "IC5") (pin "1") (pinfunction "~{MCLR}_1") (pintype "input"))
      (node (ref "ICSP") (pin "5") (pinfunction "5_5") (pintype "passive"))
      (node (ref "R1") (pin "2") (pinfunction "2_2") (pintype "passive"))
    )
  )
)
